# V1_0.net
KiCad netlist of a schematic drawn in Altium Designer
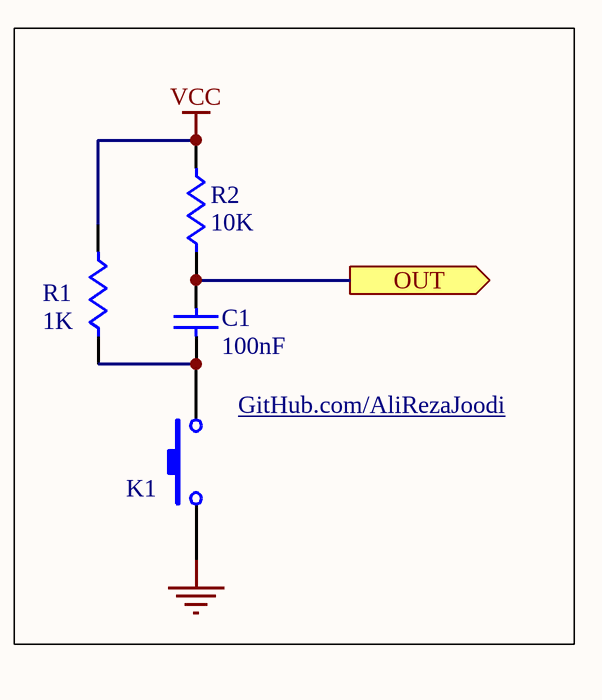
[diagram p0: V1.0.SchDoc]

(export (version "E")
  (design (tool "Eeschema 10.0.6"))
  (components
    (comp (ref "C1")
      (value "100nF")
      (footprint "CAPNTO2.54-3.56x2.03")
      (description "Capacitor")
      (fields (field (name "MANUFACTURER") "Generic Components") (field (name "PUBLISHER") "Altium Limited"))
      (libsource (lib "Miscellaneous Devices") (part "Cap"))
    )
    (comp (ref "K1")
      (value "SW-PB")
      (footprint "SPST-2_2")
      (description "Switch")
      (fields (field (name "MANUFACTURER") "Generic Components") (field (name "PUBLISHER") "Altium Limited"))
      (libsource (lib "Miscellaneous Devices") (part "SW-PB"))
    )
    (comp (ref "R1")
      (value "1K")
      (footprint "AXIAL-0.4")
      (description "Resistor")
      (fields (field (name "MANUFACTURER") "Generic Components") (field (name "PUBLISHER") "Altium Limited"))
      (libsource (lib "Miscellaneous Devices") (part "Res1"))
    )
    (comp (ref "R2")
      (value "10K")
      (footprint "AXIAL-0.4")
      (description "Resistor")
      (fields (field (name "MANUFACTURER") "Generic Components") (field (name "PUBLISHER") "Altium Limited"))
      (libsource (lib "Miscellaneous Devices") (part "Res1"))
    )
  )
  (nets
    (net (code "1") (name "/OUT") (class "Default")
      (node (ref "C1") (pin "1") (pinfunction "1_1") (pintype "passive"))
      (node (ref "R2") (pin "1") (pinfunction "1_1") (pintype "passive"))
    )
    (net (code "2") (name "GND") (class "Default")
      (node (ref "K1") (pin "1") (pinfunction "1_1") (pintype "passive"))
    )
    (net (code "3") (name "Net-(C1-Pad2)") (class "Default")
      (node (ref "C1") (pin "2") (pinfunction "2_2") (pintype "passive"))
      (node (ref "K1") (pin "2") (pinfunction "2_2") (pintype "passive"))
      (node (ref "R1") (pin "1") (pinfunction "1_1") (pintype "passive"))
    )
    (net (code "4") (name "VCC") (class "Default")
      (node (ref "R1") (pin "2") (pinfunction "2_2") (pintype "passive"))
      (node (ref "R2") (pin "2") (pinfunction "2_2") (pintype "passive"))
    )
  )
)
